# MD_260w.net
KiCad netlist of a schematic drawn in EAGLE
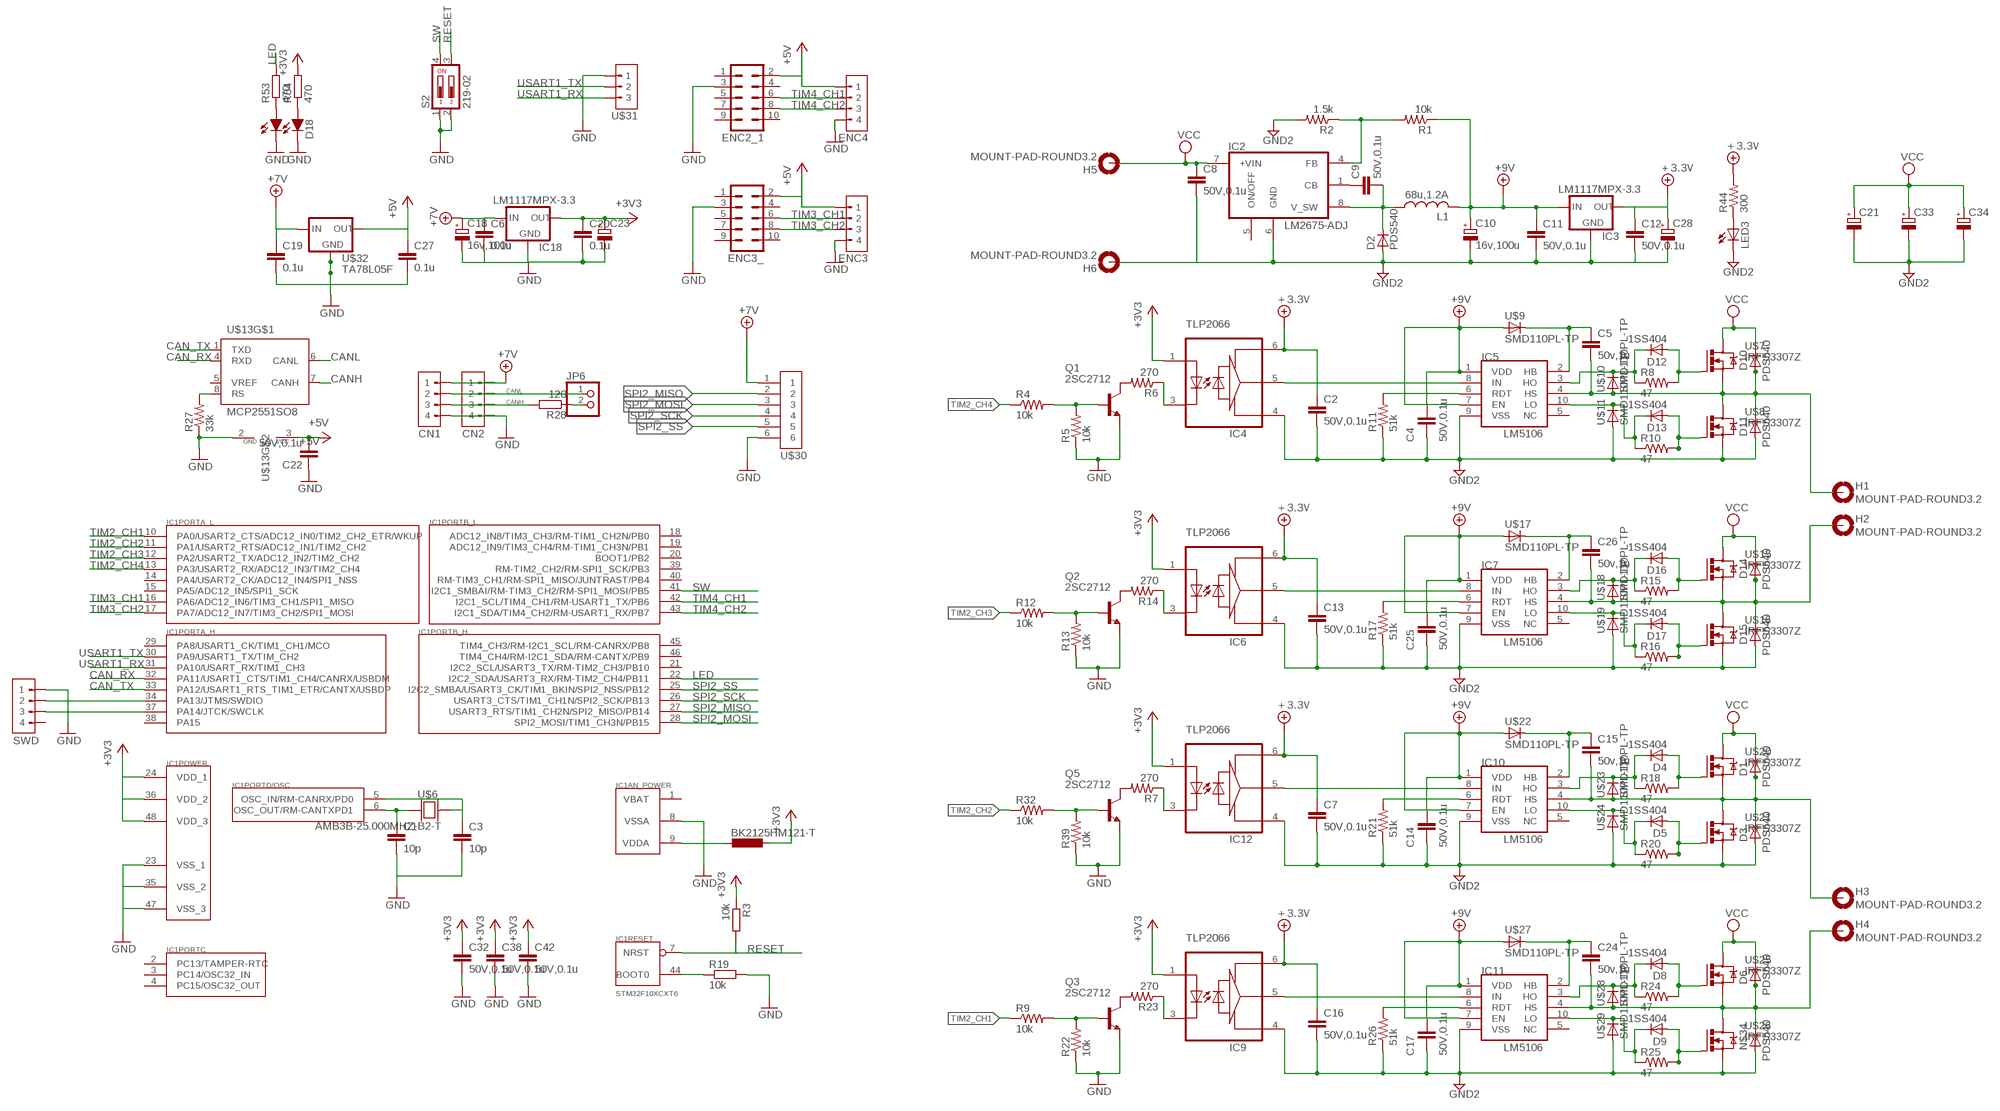
[diagram p0: schematic, sheet 1]

(export (version "E")
  (design (tool "Eeschema 10.0.6"))
  (components
    (comp (ref "BK2125HM121-T")
      (value "L-EUL2012C")
      (footprint "eagle-import:L2012C")
      (libsource (lib "eagle-import") (part "L-EUL2012C"))
    )
    (comp (ref "C1")
      (value "10p")
      (footprint "eagle-import:C0603")
      (libsource (lib "eagle-import") (part "C-EUC0603"))
    )
    (comp (ref "C2")
      (value "50V,0.1u")
      (footprint "eagle-import:C0603")
      (libsource (lib "eagle-import") (part "C-EUC0603"))
    )
    (comp (ref "C3")
      (value "10p")
      (footprint "eagle-import:C0603")
      (libsource (lib "eagle-import") (part "C-EUC0603"))
    )
    (comp (ref "C4")
      (value "50V,0.1u")
      (footprint "eagle-import:C0603")
      (libsource (lib "eagle-import") (part "C-EUC0603"))
    )
    (comp (ref "C5")
      (value "50v,1u")
      (footprint "eagle-import:C0603")
      (libsource (lib "eagle-import") (part "C-EUC0603"))
    )
    (comp (ref "C6")
      (value "0.1u")
      (footprint "eagle-import:C0603")
      (libsource (lib "eagle-import") (part "C-EUC0603"))
    )
    (comp (ref "C7")
      (value "50V,0.1u")
      (footprint "eagle-import:C0603")
      (libsource (lib "eagle-import") (part "C-EUC0603"))
    )
    (comp (ref "C8")
      (value "50V,0.1u")
      (footprint "eagle-import:C0603")
      (libsource (lib "eagle-import") (part "C-EUC0603"))
    )
    (comp (ref "C9")
      (value "50V,0.1u")
      (footprint "eagle-import:C0603")
      (libsource (lib "eagle-import") (part "C-EUC0603"))
    )
    (comp (ref "C10")
      (value "16v,100u")
      (footprint "eagle-import:153CLV-0605")
      (libsource (lib "eagle-import") (part "CPOL-EU153CLV-0605"))
    )
    (comp (ref "C11")
      (value "50V,0.1u")
      (footprint "eagle-import:C0603")
      (libsource (lib "eagle-import") (part "C-EUC0603"))
    )
    (comp (ref "C12")
      (value "50V,0.1u")
      (footprint "eagle-import:C0603")
      (libsource (lib "eagle-import") (part "C-EUC0603"))
    )
    (comp (ref "C13")
      (value "50V,0.1u")
      (footprint "eagle-import:C0603")
      (libsource (lib "eagle-import") (part "C-EUC0603"))
    )
    (comp (ref "C14")
      (value "50V,0.1u")
      (footprint "eagle-import:C0603")
      (libsource (lib "eagle-import") (part "C-EUC0603"))
    )
    (comp (ref "C15")
      (value "50v,1u")
      (footprint "eagle-import:C0603")
      (libsource (lib "eagle-import") (part "C-EUC0603"))
    )
    (comp (ref "C16")
      (value "50V,0.1u")
      (footprint "eagle-import:C0603")
      (libsource (lib "eagle-import") (part "C-EUC0603"))
    )
    (comp (ref "C17")
      (value "50V,0.1u")
      (footprint "eagle-import:C0603")
      (libsource (lib "eagle-import") (part "C-EUC0603"))
    )
    (comp (ref "C18")
      (value "16v,100u")
      (footprint "eagle-import:153CLV-0605")
      (libsource (lib "eagle-import") (part "CPOL-EU153CLV-0605"))
    )
    (comp (ref "C19")
      (value "0.1u")
      (footprint "eagle-import:C0603")
      (libsource (lib "eagle-import") (part "C-EUC0603"))
    )
    (comp (ref "C20")
      (value "0.1u")
      (footprint "eagle-import:C0603K")
      (libsource (lib "eagle-import") (part "resistor_C-EUC0603K"))
    )
    (comp (ref "C21")
      (value "CPOL-EUE7.5-16")
      (footprint "eagle-import:E7,5-16")
      (libsource (lib "eagle-import") (part "CPOL-EUE7.5-16"))
    )
    (comp (ref "C22")
      (value "50V,0.1u")
      (footprint "eagle-import:C0603")
      (libsource (lib "eagle-import") (part "C-EUC0603"))
    )
    (comp (ref "C23")
      (value "CPOL-EU153CLV-0505")
      (footprint "eagle-import:153CLV-0505")
      (libsource (lib "eagle-import") (part "CPOL-EU153CLV-0505"))
    )
    (comp (ref "C24")
      (value "50v,1u")
      (footprint "eagle-import:C0603")
      (libsource (lib "eagle-import") (part "C-EUC0603"))
    )
    (comp (ref "C25")
      (value "50V,0.1u")
      (footprint "eagle-import:C0603")
      (libsource (lib "eagle-import") (part "C-EUC0603"))
    )
    (comp (ref "C26")
      (value "50v,1u")
      (footprint "eagle-import:C0603")
      (libsource (lib "eagle-import") (part "C-EUC0603"))
    )
    (comp (ref "C27")
      (value "0.1u")
      (footprint "eagle-import:C0603")
      (libsource (lib "eagle-import") (part "C-EUC0603"))
    )
    (comp (ref "C28")
      (value "CPOL-EU153CLV-0505")
      (footprint "eagle-import:153CLV-0505")
      (libsource (lib "eagle-import") (part "CPOL-EU153CLV-0505"))
    )
    (comp (ref "C32")
      (value "50V,0.1u")
      (footprint "eagle-import:C0603K")
      (libsource (lib "eagle-import") (part "resistor_C-EUC0603K"))
    )
    (comp (ref "C33")
      (value "CPOL-EUE7.5-16")
      (footprint "eagle-import:E7,5-16")
      (libsource (lib "eagle-import") (part "CPOL-EUE7.5-16"))
    )
    (comp (ref "C34")
      (value "CPOL-EUE7.5-16")
      (footprint "eagle-import:E7,5-16")
      (libsource (lib "eagle-import") (part "CPOL-EUE7.5-16"))
    )
    (comp (ref "C38")
      (value "50V,0.1u")
      (footprint "eagle-import:C0603K")
      (libsource (lib "eagle-import") (part "resistor_C-EUC0603K"))
    )
    (comp (ref "C42")
      (value "50V,0.1u")
      (footprint "eagle-import:C0603K")
      (libsource (lib "eagle-import") (part "resistor_C-EUC0603K"))
    )
    (comp (ref "CN1")
      (value "CN4-JST-XH-TOP")
      (footprint "eagle-import:JST-B4B-XH-A")
      (libsource (lib "eagle-import") (part "CN4-JST-XH-TOP"))
    )
    (comp (ref "CN2")
      (value "CN4-JST-XH-TOP")
      (footprint "eagle-import:JST-B4B-XH-A")
      (libsource (lib "eagle-import") (part "CN4-JST-XH-TOP"))
    )
    (comp (ref "D1")
      (value "PDS540")
      (footprint "eagle-import:POWER_DI_5")
      (libsource (lib "eagle-import") (part "PDS540"))
    )
    (comp (ref "D2")
      (value "PDS540")
      (footprint "eagle-import:POWER_DI_5")
      (libsource (lib "eagle-import") (part "PDS540"))
    )
    (comp (ref "D3")
      (value "PDS540")
      (footprint "eagle-import:POWER_DI_5")
      (libsource (lib "eagle-import") (part "PDS540"))
    )
    (comp (ref "D4")
      (value "1SS404")
      (footprint "eagle-import:USC(1.25X2.5)")
      (libsource (lib "eagle-import") (part "1SS404"))
    )
    (comp (ref "D5")
      (value "1SS404")
      (footprint "eagle-import:USC(1.25X2.5)")
      (libsource (lib "eagle-import") (part "1SS404"))
    )
    (comp (ref "D6")
      (value "PDS540")
      (footprint "eagle-import:POWER_DI_5")
      (libsource (lib "eagle-import") (part "PDS540"))
    )
    (comp (ref "D8")
      (value "1SS404")
      (footprint "eagle-import:USC(1.25X2.5)")
      (libsource (lib "eagle-import") (part "1SS404"))
    )
    (comp (ref "D9")
      (value "1SS404")
      (footprint "eagle-import:USC(1.25X2.5)")
      (libsource (lib "eagle-import") (part "1SS404"))
    )
    (comp (ref "D10")
      (value "PDS540")
      (footprint "eagle-import:POWER_DI_5")
      (libsource (lib "eagle-import") (part "PDS540"))
    )
    (comp (ref "D11")
      (value "PDS540")
      (footprint "eagle-import:POWER_DI_5")
      (libsource (lib "eagle-import") (part "PDS540"))
    )
    (comp (ref "D12")
      (value "1SS404")
      (footprint "eagle-import:USC(1.25X2.5)")
      (libsource (lib "eagle-import") (part "1SS404"))
    )
    (comp (ref "D13")
      (value "1SS404")
      (footprint "eagle-import:USC(1.25X2.5)")
      (libsource (lib "eagle-import") (part "1SS404"))
    )
    (comp (ref "D14")
      (value "PDS540")
      (footprint "eagle-import:POWER_DI_5")
      (libsource (lib "eagle-import") (part "PDS540"))
    )
    (comp (ref "D15")
      (value "PDS540")
      (footprint "eagle-import:POWER_DI_5")
      (libsource (lib "eagle-import") (part "PDS540"))
    )
    (comp (ref "D16")
      (value "1SS404")
      (footprint "eagle-import:USC(1.25X2.5)")
      (libsource (lib "eagle-import") (part "1SS404"))
    )
    (comp (ref "D17")
      (value "1SS404")
      (footprint "eagle-import:USC(1.25X2.5)")
      (libsource (lib "eagle-import") (part "1SS404"))
    )
    (comp (ref "D18")
      (value "SEC2XX4")
      (footprint "eagle-import:LED3025")
      (libsource (lib "eagle-import") (part "SEC2XX4"))
    )
    (comp (ref "ENC2_1")
      (value "ML10L")
      (footprint "eagle-import:ML10L")
      (libsource (lib "eagle-import") (part "ML10L"))
    )
    (comp (ref "ENC3")
      (value "CN4-JST-XH-TOP")
      (footprint "eagle-import:JST-B4B-XH-A")
      (libsource (lib "eagle-import") (part "CN4-JST-XH-TOP"))
    )
    (comp (ref "ENC3_")
      (value "ML10L")
      (footprint "eagle-import:ML10L")
      (libsource (lib "eagle-import") (part "ML10L"))
    )
    (comp (ref "ENC4")
      (value "CN4-JST-XH-TOP")
      (footprint "eagle-import:JST-B4B-XH-A")
      (libsource (lib "eagle-import") (part "CN4-JST-XH-TOP"))
    )
    (comp (ref "H1")
      (value "MOUNT-PAD-ROUND3.2")
      (footprint "eagle-import:3,2-PAD")
      (libsource (lib "eagle-import") (part "MOUNT-PAD-ROUND3.2"))
    )
    (comp (ref "H2")
      (value "MOUNT-PAD-ROUND3.2")
      (footprint "eagle-import:3,2-PAD")
      (libsource (lib "eagle-import") (part "MOUNT-PAD-ROUND3.2"))
    )
    (comp (ref "H3")
      (value "MOUNT-PAD-ROUND3.2")
      (footprint "eagle-import:3,2-PAD")
      (libsource (lib "eagle-import") (part "MOUNT-PAD-ROUND3.2"))
    )
    (comp (ref "H4")
      (value "MOUNT-PAD-ROUND3.2")
      (footprint "eagle-import:3,2-PAD")
      (libsource (lib "eagle-import") (part "MOUNT-PAD-ROUND3.2"))
    )
    (comp (ref "H5")
      (value "MOUNT-PAD-ROUND3.2")
      (footprint "eagle-import:3,2-PAD")
      (libsource (lib "eagle-import") (part "MOUNT-PAD-ROUND3.2"))
    )
    (comp (ref "H6")
      (value "MOUNT-PAD-ROUND3.2")
      (footprint "eagle-import:3,2-PAD")
      (libsource (lib "eagle-import") (part "MOUNT-PAD-ROUND3.2"))
    )
    (comp (ref "IC1")
      (value "STM32F10XCXT6")
      (footprint "eagle-import:TQFP48")
      (libsource (lib "eagle-import") (part "STM32F10XCXT6"))
    )
    (comp (ref "IC2")
      (value "LM2675-ADJ")
      (footprint "eagle-import:SOP8-150")
      (libsource (lib "eagle-import") (part "LM2675"))
    )
    (comp (ref "IC3")
      (value "LM1117MPX-3.3")
      (footprint "eagle-import:SOT223")
      (libsource (lib "eagle-import") (part "LM1117"))
    )
    (comp (ref "IC4")
      (value "TLP2066")
      (footprint "eagle-import:MFSOP6")
      (libsource (lib "eagle-import") (part "TLP117"))
    )
    (comp (ref "IC5")
      (value "LM5106")
      (footprint "eagle-import:MSOP10")
      (libsource (lib "eagle-import") (part "LM5106"))
    )
    (comp (ref "IC6")
      (value "TLP2066")
      (footprint "eagle-import:MFSOP6")
      (libsource (lib "eagle-import") (part "TLP117"))
    )
    (comp (ref "IC7")
      (value "LM5106")
      (footprint "eagle-import:MSOP10")
      (libsource (lib "eagle-import") (part "LM5106"))
    )
    (comp (ref "IC9")
      (value "TLP2066")
      (footprint "eagle-import:MFSOP6")
      (libsource (lib "eagle-import") (part "TLP117"))
    )
    (comp (ref "IC10")
      (value "LM5106")
      (footprint "eagle-import:MSOP10")
      (libsource (lib "eagle-import") (part "LM5106"))
    )
    (comp (ref "IC11")
      (value "LM5106")
      (footprint "eagle-import:MSOP10")
      (libsource (lib "eagle-import") (part "LM5106"))
    )
    (comp (ref "IC12")
      (value "TLP2066")
      (footprint "eagle-import:MFSOP6")
      (libsource (lib "eagle-import") (part "TLP117"))
    )
    (comp (ref "IC18")
      (value "LM1117MPX-3.3")
      (footprint "eagle-import:SOT223")
      (libsource (lib "eagle-import") (part "LM1117"))
    )
    (comp (ref "JP6")
      (value "PINHD-1X2")
      (footprint "eagle-import:1X02")
      (libsource (lib "eagle-import") (part "PINHD-1X2"))
    )
    (comp (ref "L1")
      (value "68u,1.2A")
      (footprint "eagle-import:SLF10145")
      (libsource (lib "eagle-import") (part "SLF10145T"))
    )
    (comp (ref "LED3")
      (value "0603")
      (footprint "eagle-import:0603")
      (libsource (lib "eagle-import") (part "0603"))
    )
    (comp (ref "N$34")
      (value "PDS540")
      (footprint "eagle-import:POWER_DI_5")
      (libsource (lib "eagle-import") (part "PDS540"))
    )
    (comp (ref "Q1")
      (value "2SC2712")
      (footprint "eagle-import:SC-59(TYPE1)")
      (libsource (lib "eagle-import") (part "2SC2712"))
    )
    (comp (ref "Q2")
      (value "2SC2712")
      (footprint "eagle-import:SC-59(TYPE1)")
      (libsource (lib "eagle-import") (part "2SC2712"))
    )
    (comp (ref "Q3")
      (value "2SC2712")
      (footprint "eagle-import:SC-59(TYPE1)")
      (libsource (lib "eagle-import") (part "2SC2712"))
    )
    (comp (ref "Q5")
      (value "2SC2712")
      (footprint "eagle-import:SC-59(TYPE1)")
      (libsource (lib "eagle-import") (part "2SC2712"))
    )
    (comp (ref "R1")
      (value "10k")
      (footprint "eagle-import:R0603")
      (libsource (lib "eagle-import") (part "resistor_R-US_R0603"))
    )
    (comp (ref "R2")
      (value "1.5k")
      (footprint "eagle-import:R0603")
      (libsource (lib "eagle-import") (part "resistor_R-US_R0603"))
    )
    (comp (ref "R3")
      (value "10k")
      (footprint "eagle-import:R0603")
      (libsource (lib "eagle-import") (part "R-EU_R0603"))
    )
    (comp (ref "R4")
      (value "10k")
      (footprint "eagle-import:R0603")
      (libsource (lib "eagle-import") (part "resistor_R-US_R0603"))
    )
    (comp (ref "R5")
      (value "10k")
      (footprint "eagle-import:R0603")
      (libsource (lib "eagle-import") (part "resistor_R-US_R0603"))
    )
    (comp (ref "R6")
      (value "270")
      (footprint "eagle-import:R0603")
      (libsource (lib "eagle-import") (part "resistor_R-US_R0603"))
    )
    (comp (ref "R7")
      (value "270")
      (footprint "eagle-import:R0603")
      (libsource (lib "eagle-import") (part "resistor_R-US_R0603"))
    )
    (comp (ref "R8")
      (value "47")
      (footprint "eagle-import:R0603")
      (libsource (lib "eagle-import") (part "resistor_R-US_R0603"))
    )
    (comp (ref "R9")
      (value "10k")
      (footprint "eagle-import:R0603")
      (libsource (lib "eagle-import") (part "resistor_R-US_R0603"))
    )
    (comp (ref "R10")
      (value "47")
      (footprint "eagle-import:R0603")
      (libsource (lib "eagle-import") (part "resistor_R-US_R0603"))
    )
    (comp (ref "R11")
      (value "51k")
      (footprint "eagle-import:R0603")
      (libsource (lib "eagle-import") (part "R-US_R0603"))
    )
    (comp (ref "R12")
      (value "10k")
      (footprint "eagle-import:R0603")
      (libsource (lib "eagle-import") (part "resistor_R-US_R0603"))
    )
    (comp (ref "R13")
      (value "10k")
      (footprint "eagle-import:R0603")
      (libsource (lib "eagle-import") (part "resistor_R-US_R0603"))
    )
    (comp (ref "R14")
      (value "270")
      (footprint "eagle-import:R0603")
      (libsource (lib "eagle-import") (part "resistor_R-US_R0603"))
    )
    (comp (ref "R15")
      (value "47")
      (footprint "eagle-import:R0603")
      (libsource (lib "eagle-import") (part "resistor_R-US_R0603"))
    )
    (comp (ref "R16")
      (value "47")
      (footprint "eagle-import:R0603")
      (libsource (lib "eagle-import") (part "resistor_R-US_R0603"))
    )
    (comp (ref "R17")
      (value "51k")
      (footprint "eagle-import:R0603")
      (libsource (lib "eagle-import") (part "R-US_R0603"))
    )
    (comp (ref "R18")
      (value "47")
      (footprint "eagle-import:R0603")
      (libsource (lib "eagle-import") (part "resistor_R-US_R0603"))
    )
    (comp (ref "R19")
      (value "10k")
      (footprint "eagle-import:R0603")
      (libsource (lib "eagle-import") (part "R-EU_R0603"))
    )
    (comp (ref "R20")
      (value "47")
      (footprint "eagle-import:R0603")
      (libsource (lib "eagle-import") (part "resistor_R-US_R0603"))
    )
    (comp (ref "R21")
      (value "51k")
      (footprint "eagle-import:R0603")
      (libsource (lib "eagle-import") (part "R-US_R0603"))
    )
    (comp (ref "R22")
      (value "10k")
      (footprint "eagle-import:R0603")
      (libsource (lib "eagle-import") (part "resistor_R-US_R0603"))
    )
    (comp (ref "R23")
      (value "270")
      (footprint "eagle-import:R0603")
      (libsource (lib "eagle-import") (part "resistor_R-US_R0603"))
    )
    (comp (ref "R24")
      (value "47")
      (footprint "eagle-import:R0603")
      (libsource (lib "eagle-import") (part "resistor_R-US_R0603"))
    )
    (comp (ref "R25")
      (value "47")
      (footprint "eagle-import:R0603")
      (libsource (lib "eagle-import") (part "resistor_R-US_R0603"))
    )
    (comp (ref "R26")
      (value "51k")
      (footprint "eagle-import:R0603")
      (libsource (lib "eagle-import") (part "R-US_R0603"))
    )
    (comp (ref "R27")
      (value "33k")
      (footprint "eagle-import:R0603")
      (libsource (lib "eagle-import") (part "resistor_R-US_R0603"))
    )
    (comp (ref "R28")
      (value "120")
      (footprint "eagle-import:R0603")
      (libsource (lib "eagle-import") (part "resistor_R-EU_R0603"))
    )
    (comp (ref "R32")
      (value "10k")
      (footprint "eagle-import:R0603")
      (libsource (lib "eagle-import") (part "resistor_R-US_R0603"))
    )
    (comp (ref "R39")
      (value "10k")
      (footprint "eagle-import:R0603")
      (libsource (lib "eagle-import") (part "resistor_R-US_R0603"))
    )
    (comp (ref "R44")
      (value "300")
      (footprint "eagle-import:R0603")
      (libsource (lib "eagle-import") (part "resistor_R-US_R0603"))
    )
    (comp (ref "R53")
      (value "470")
      (footprint "eagle-import:R0603")
      (libsource (lib "eagle-import") (part "resistor_R-EU_R0603"))
    )
    (comp (ref "R54")
      (value "470")
      (footprint "eagle-import:R0603")
      (libsource (lib "eagle-import") (part "resistor_R-EU_R0603"))
    )
    (comp (ref "S2")
      (value "219-02")
      (footprint "eagle-import:CTS-219-02")
      (libsource (lib "eagle-import") (part "219-02"))
    )
    (comp (ref "SWD")
      (value "TOP_TYPE_4PIN")
      (footprint "eagle-import:TOP_TYPE_4PIN")
      (libsource (lib "eagle-import") (part "TOP_TYPE_4PIN"))
    )
    (comp (ref "U$6")
      (value "AMB3B-25.000MHZ-B2-T")
      (footprint "eagle-import:4LCC")
      (libsource (lib "eagle-import") (part "AMB3B-25.000MHZ-B2-T"))
    )
    (comp (ref "U$7")
      (value "IRFS3307Z")
      (footprint "eagle-import:IRFS3307Z")
      (libsource (lib "eagle-import") (part "IRFS3307Z"))
    )
    (comp (ref "U$8")
      (value "IRFS3307Z")
      (footprint "eagle-import:IRFS3307Z")
      (libsource (lib "eagle-import") (part "IRFS3307Z"))
    )
    (comp (ref "U$9")
      (value "SMD110PL-TP")
      (footprint "eagle-import:SOD123")
      (libsource (lib "eagle-import") (part "SMD110PL-TP"))
    )
    (comp (ref "U$10")
      (value "SMD110PL-TP")
      (footprint "eagle-import:SOD123")
      (libsource (lib "eagle-import") (part "SMD110PL-TP"))
    )
    (comp (ref "U$11")
      (value "SMD110PL-TP")
      (footprint "eagle-import:SOD123")
      (libsource (lib "eagle-import") (part "SMD110PL-TP"))
    )
    (comp (ref "U$13")
      (value "MCP2551SO8")
      (footprint "eagle-import:SO08")
      (libsource (lib "eagle-import") (part "MCP2551SO8"))
    )
    (comp (ref "U$15")
      (value "IRFS3307Z")
      (footprint "eagle-import:IRFS3307Z")
      (libsource (lib "eagle-import") (part "IRFS3307Z"))
    )
    (comp (ref "U$16")
      (value "IRFS3307Z")
      (footprint "eagle-import:IRFS3307Z")
      (libsource (lib "eagle-import") (part "IRFS3307Z"))
    )
    (comp (ref "U$17")
      (value "SMD110PL-TP")
      (footprint "eagle-import:SOD123")
      (libsource (lib "eagle-import") (part "SMD110PL-TP"))
    )
    (comp (ref "U$18")
      (value "SMD110PL-TP")
      (footprint "eagle-import:SOD123")
      (libsource (lib "eagle-import") (part "SMD110PL-TP"))
    )
    (comp (ref "U$19")
      (value "SMD110PL-TP")
      (footprint "eagle-import:SOD123")
      (libsource (lib "eagle-import") (part "SMD110PL-TP"))
    )
    (comp (ref "U$20")
      (value "IRFS3307Z")
      (footprint "eagle-import:IRFS3307Z")
      (libsource (lib "eagle-import") (part "IRFS3307Z"))
    )
    (comp (ref "U$21")
      (value "IRFS3307Z")
      (footprint "eagle-import:IRFS3307Z")
      (libsource (lib "eagle-import") (part "IRFS3307Z"))
    )
    (comp (ref "U$22")
      (value "SMD110PL-TP")
      (footprint "eagle-import:SOD123")
      (libsource (lib "eagle-import") (part "SMD110PL-TP"))
    )
    (comp (ref "U$23")
      (value "SMD110PL-TP")
      (footprint "eagle-import:SOD123")
      (libsource (lib "eagle-import") (part "SMD110PL-TP"))
    )
    (comp (ref "U$24")
      (value "SMD110PL-TP")
      (footprint "eagle-import:SOD123")
      (libsource (lib "eagle-import") (part "SMD110PL-TP"))
    )
    (comp (ref "U$25")
      (value "IRFS3307Z")
      (footprint "eagle-import:IRFS3307Z")
      (libsource (lib "eagle-import") (part "IRFS3307Z"))
    )
    (comp (ref "U$26")
      (value "IRFS3307Z")
      (footprint "eagle-import:IRFS3307Z")
      (libsource (lib "eagle-import") (part "IRFS3307Z"))
    )
    (comp (ref "U$27")
      (value "SMD110PL-TP")
      (footprint "eagle-import:SOD123")
      (libsource (lib "eagle-import") (part "SMD110PL-TP"))
    )
    (comp (ref "U$28")
      (value "SMD110PL-TP")
      (footprint "eagle-import:SOD123")
      (libsource (lib "eagle-import") (part "SMD110PL-TP"))
    )
    (comp (ref "U$29")
      (value "SMD110PL-TP")
      (footprint "eagle-import:SOD123")
      (libsource (lib "eagle-import") (part "SMD110PL-TP"))
    )
    (comp (ref "U$30")
      (value "CN6")
      (footprint "eagle-import:JST-B6B-XH-A")
      (libsource (lib "eagle-import") (part "CN6"))
    )
    (comp (ref "U$31")
      (value "TOP_TYPE_3PIN")
      (footprint "eagle-import:TOP_TYPE_3PIN")
      (libsource (lib "eagle-import") (part "TOP_TYPE_3PIN"))
    )
    (comp (ref "U$32")
      (value "TA78L05F")
      (footprint "eagle-import:SOT89")
      (libsource (lib "eagle-import") (part "TA78L05F"))
    )
  )
  (nets
    (net (code "1") (name "+3V3") (class "Default")
      (node (ref "BK2125HM121-T") (pin "1") (pinfunction "1_1") (pintype "passive"))
      (node (ref "C20") (pin "1") (pinfunction "1_1") (pintype "passive"))
      (node (ref "C23") (pin "+") (pinfunction "+_+") (pintype "passive"))
      (node (ref "C32") (pin "1") (pinfunction "1_1") (pintype "passive"))
      (node (ref "C38") (pin "1") (pinfunction "1_1") (pintype "passive"))
      (node (ref "C42") (pin "1") (pinfunction "1_1") (pintype "passive"))
      (node (ref "IC1") (pin "24") (pinfunction "VDD_1_24") (pintype "power_in"))
      (node (ref "IC1") (pin "36") (pinfunction "VDD_2_36") (pintype "power_in"))
      (node (ref "IC1") (pin "48") (pinfunction "VDD_3_48") (pintype "power_in"))
      (node (ref "IC12") (pin "1") (pinfunction "1_1") (pintype "input"))
      (node (ref "IC18") (pin "2") (pinfunction "OUT1_2") (pintype "passive"))
      (node (ref "IC18") (pin "4") (pinfunction "OUT_4") (pintype "passive"))
      (node (ref "IC4") (pin "1") (pinfunction "1_1") (pintype "input"))
      (node (ref "IC6") (pin "1") (pinfunction "1_1") (pintype "input"))
      (node (ref "IC9") (pin "1") (pinfunction "1_1") (pintype "input"))
      (node (ref "R3") (pin "1") (pinfunction "1_1") (pintype "passive"))
      (node (ref "R54") (pin "2") (pinfunction "2_2") (pintype "passive"))
    )
    (net (code "2") (name "+5V") (class "Default")
      (node (ref "C22") (pin "2") (pinfunction "2_2") (pintype "passive"))
      (node (ref "C27") (pin "1") (pinfunction "1_1") (pintype "passive"))
      (node (ref "ENC2_1") (pin "2") (pinfunction "2_2") (pintype "passive"))
      (node (ref "ENC3") (pin "1") (pinfunction "1_1") (pintype "passive"))
      (node (ref "ENC3_") (pin "2") (pinfunction "2_2") (pintype "passive"))
      (node (ref "ENC4") (pin "1") (pinfunction "1_1") (pintype "passive"))
      (node (ref "U$13") (pin "3") (pinfunction "VCC_3") (pintype "power_in"))
      (node (ref "U$32") (pin "1") (pinfunction "OUT_1") (pintype "passive"))
    )
    (net (code "3") (name "+7V") (class "Default")
      (node (ref "C18") (pin "+") (pinfunction "+_+") (pintype "passive"))
      (node (ref "C19") (pin "1") (pinfunction "1_1") (pintype "passive"))
      (node (ref "C6") (pin "1") (pinfunction "1_1") (pintype "passive"))
      (node (ref "CN1") (pin "1") (pinfunction "1_1") (pintype "passive"))
      (node (ref "CN2") (pin "1") (pinfunction "1_1") (pintype "passive"))
      (node (ref "IC18") (pin "3") (pinfunction "IN_3") (pintype "input"))
      (node (ref "U$30") (pin "1") (pinfunction "1_1") (pintype "passive"))
      (node (ref "U$32") (pin "3") (pinfunction "IN_3") (pintype "input"))
    )
    (net (code "4") (name "+9V") (class "Default")
      (node (ref "C10") (pin "+") (pinfunction "+_+") (pintype "passive"))
      (node (ref "C11") (pin "1") (pinfunction "1_1") (pintype "passive"))
      (node (ref "C14") (pin "1") (pinfunction "1_1") (pintype "passive"))
      (node (ref "C17") (pin "1") (pinfunction "1_1") (pintype "passive"))
      (node (ref "C25") (pin "1") (pinfunction "1_1") (pintype "passive"))
      (node (ref "C4") (pin "1") (pinfunction "1_1") (pintype "passive"))
      (node (ref "IC10") (pin "1") (pinfunction "VDD_1") (pintype "power_in"))
      (node (ref "IC10") (pin "7") (pinfunction "EN_7") (pintype "input"))
      (node (ref "IC11") (pin "1") (pinfunction "VDD_1") (pintype "power_in"))
      (node (ref "IC11") (pin "7") (pinfunction "EN_7") (pintype "input"))
      (node (ref "IC3") (pin "3") (pinfunction "IN_3") (pintype "input"))
      (node (ref "IC5") (pin "1") (pinfunction "VDD_1") (pintype "power_in"))
      (node (ref "IC5") (pin "7") (pinfunction "EN_7") (pintype "input"))
      (node (ref "IC7") (pin "1") (pinfunction "VDD_1") (pintype "power_in"))
      (node (ref "IC7") (pin "7") (pinfunction "EN_7") (pintype "input"))
      (node (ref "L1") (pin "P$2") (pinfunction "2_P$2") (pintype "passive"))
      (node (ref "R1") (pin "1") (pinfunction "1_1") (pintype "passive"))
      (node (ref "U$17") (pin "A") (pinfunction "A_A") (pintype "passive"))
      (node (ref "U$22") (pin "A") (pinfunction "A_A") (pintype "passive"))
      (node (ref "U$27") (pin "A") (pinfunction "A_A") (pintype "passive"))
      (node (ref "U$9") (pin "A") (pinfunction "A_A") (pintype "passive"))
    )
    (net (code "5") (name "/CANH") (class "Default")
      (node (ref "CN1") (pin "3") (pinfunction "3_3") (pintype "passive"))
      (node (ref "CN2") (pin "3") (pinfunction "3_3") (pintype "passive"))
      (node (ref "R28") (pin "2") (pinfunction "2_2") (pintype "passive"))
      (node (ref "U$13") (pin "7") (pinfunction "CANH_7") (pintype "bidirectional"))
    )
    (net (code "6") (name "/CANL") (class "Default")
      (node (ref "CN1") (pin "2") (pinfunction "2_2") (pintype "passive"))
      (node (ref "CN2") (pin "2") (pinfunction "2_2") (pintype "passive"))
      (node (ref "JP6") (pin "1") (pinfunction "1_1") (pintype "passive"))
      (node (ref "U$13") (pin "6") (pinfunction "CANL_6") (pintype "bidirectional"))
    )
    (net (code "7") (name "/CAN_RX") (class "Default")
      (node (ref "IC1") (pin "32") (pinfunction "PA11/USART1_CTS/TIM1_CH4/CANRX/USBDM_32") (pintype "bidirectional"))
      (node (ref "U$13") (pin "4") (pinfunction "RXD_4") (pintype "bidirectional"))
    )
    (net (code "8") (name "/CAN_TX") (class "Default")
      (node (ref "IC1") (pin "33") (pinfunction "PA12/USART1_RTS_TIM1_ETR/CANTX/USBDP_33") (pintype "bidirectional"))
      (node (ref "U$13") (pin "1") (pinfunction "TXD_1") (pintype "bidirectional"))
    )
    (net (code "9") (name "/LED") (class "Default")
      (node (ref "IC1") (pin "22") (pinfunction "I2C2_SDA/USART3_RX/RM-TIM2_CH4/PB11_22") (pintype "bidirectional"))
      (node (ref "R53") (pin "2") (pinfunction "2_2") (pintype "passive"))
    )
    (net (code "10") (name "/RESET") (class "Default")
      (node (ref "IC1") (pin "7") (pinfunction "NRST_7") (pintype "input"))
      (node (ref "R3") (pin "2") (pinfunction "2_2") (pintype "passive"))
      (node (ref "S2") (pin "3") (pinfunction "3_3") (pintype "passive"))
    )
    (net (code "11") (name "/SW") (class "Default")
      (node (ref "IC1") (pin "41") (pinfunction "I2C1_SMBAI/RM-TIM3_CH2/RM-SPI1_MOSI/PB5_41") (pintype "bidirectional"))
      (node (ref "S2") (pin "4") (pinfunction "4_4") (pintype "passive"))
    )
    (net (code "12") (name "/TIM3_CH1") (class "Default")
      (node (ref "ENC3") (pin "2") (pinfunction "2_2") (pintype "passive"))
      (node (ref "ENC3_") (pin "6") (pinfunction "6_6") (pintype "passive"))
      (node (ref "IC1") (pin "16") (pinfunction "PA6/ADC12_IN6/TIM3_CH1/SPI1_MISO_16") (pintype "bidirectional"))
    )
    (net (code "13") (name "/TIM3_CH2") (class "Default")
      (node (ref "ENC3") (pin "3") (pinfunction "3_3") (pintype "passive"))
      (node (ref "ENC3_") (pin "8") (pinfunction "8_8") (pintype "passive"))
      (node (ref "IC1") (pin "17") (pinfunction "PA7/ADC12_IN7/TIM3_CH2/SPI1_MOSI_17") (pintype "bidirectional"))
    )
    (net (code "14") (name "/TIM4_CH1") (class "Default")
      (node (ref "ENC2_1") (pin "6") (pinfunction "6_6") (pintype "passive"))
      (node (ref "ENC4") (pin "2") (pinfunction "2_2") (pintype "passive"))
      (node (ref "IC1") (pin "42") (pinfunction "I2C1_SCL/TIM4_CH1/RM-USART1_TX/PB6_42") (pintype "bidirectional"))
    )
    (net (code "15") (name "/TIM4_CH2") (class "Default")
      (node (ref "ENC2_1") (pin "8") (pinfunction "8_8") (pintype "passive"))
      (node (ref "ENC4") (pin "3") (pinfunction "3_3") (pintype "passive"))
      (node (ref "IC1") (pin "43") (pinfunction "I2C1_SDA/TIM4_CH2/RM-USART1_RX/PB7_43") (pintype "bidirectional"))
    )
    (net (code "16") (name "/USART1_RX") (class "Default")
      (node (ref "IC1") (pin "31") (pinfunction "PA10/USART_RX/TIM1_CH3_31") (pintype "bidirectional"))
      (node (ref "U$31") (pin "3") (pinfunction "3_3") (pintype "passive"))
    )
    (net (code "17") (name "/USART1_TX") (class "Default")
      (node (ref "IC1") (pin "30") (pinfunction "PA9/USART1_TX/TIM_CH2_30") (pintype "bidirectional"))
      (node (ref "U$31") (pin "2") (pinfunction "2_2") (pintype "passive"))
    )
    (net (code "18") (name "/VBAT") (class "Default")
      (node (ref "IC1") (pin "1") (pinfunction "VBAT_1") (pintype "power_in"))
    )
    (net (code "19") (name "GND") (class "Default")
      (node (ref "C1") (pin "2") (pinfunction "2_2") (pintype "passive"))
      (node (ref "C18") (pin "-") (pinfunction "-_-") (pintype "passive"))
      (node (ref "C19") (pin "2") (pinfunction "2_2") (pintype "passive"))
      (node (ref "C20") (pin "2") (pinfunction "2_2") (pintype "passive"))
      (node (ref "C22") (pin "1") (pinfunction "1_1") (pintype "passive"))
      (node (ref "C23") (pin "-") (pinfunction "-_-") (pintype "passive"))
      (node (ref "C27") (pin "2") (pinfunction "2_2") (pintype "passive"))
      (node (ref "C3") (pin "2") (pinfunction "2_2") (pintype "passive"))
      (node (ref "C32") (pin "2") (pinfunction "2_2") (pintype "passive"))
      (node (ref "C38") (pin "2") (pinfunction "2_2") (pintype "passive"))
      (node (ref "C42") (pin "2") (pinfunction "2_2") (pintype "passive"))
      (node (ref "C6") (pin "2") (pinfunction "2_2") (pintype "passive"))
      (node (ref "CN1") (pin "4") (pinfunction "4_4") (pintype "passive"))
      (node (ref "CN2") (pin "4") (pinfunction "4_4") (pintype "passive"))
      (node (ref "D18") (pin "1") (pinfunction "C0_1") (pintype "passive"))
      (node (ref "D18") (pin "2") (pinfunction "C1_2") (pintype "passive"))
      (node (ref "ENC2_1") (pin "3") (pinfunction "3_3") (pintype "passive"))
      (node (ref "ENC3") (pin "4") (pinfunction "4_4") (pintype "passive"))
      (node (ref "ENC3_") (pin "3") (pinfunction "3_3") (pintype "passive"))
      (node (ref "ENC4") (pin "4") (pinfunction "4_4") (pintype "passive"))
      (node (ref "IC1") (pin "23") (pinfunction "VSS_1_23") (pintype "power_in"))
      (node (ref "IC1") (pin "35") (pinfunction "VSS_2_35") (pintype "power_in"))
      (node (ref "IC1") (pin "47") (pinfunction "VSS_3_47") (pintype "power_in"))
      (node (ref "IC1") (pin "8") (pinfunction "VSSA_8") (pintype "power_in"))
      (node (ref "IC18") (pin "1") (pinfunction "GND_1") (pintype "input"))
      (node (ref "Q1") (pin "E") (pinfunction "E_E") (pintype "passive"))
      (node (ref "Q2") (pin "E") (pinfunction "E_E") (pintype "passive"))
      (node (ref "Q3") (pin "E") (pinfunction "E_E") (pintype "passive"))
      (node (ref "Q5") (pin "E") (pinfunction "E_E") (pintype "passive"))
      (node (ref "R13") (pin "1") (pinfunction "1_1") (pintype "passive"))
      (node (ref "R19") (pin "2") (pinfunction "2_2") (pintype "passive"))
      (node (ref "R22") (pin "1") (pinfunction "1_1") (pintype "passive"))
      (node (ref "R27") (pin "1") (pinfunction "1_1") (pintype "passive"))
      (node (ref "R39") (pin "1") (pinfunction "1_1") (pintype "passive"))
      (node (ref "R5") (pin "1") (pinfunction "1_1") (pintype "passive"))
      (node (ref "S2") (pin "1") (pinfunction "1_1") (pintype "passive"))
      (node (ref "S2") (pin "2") (pinfunction "2_2") (pintype "passive"))
      (node (ref "SWD") (pin "1") (pinfunction "1_1") (pintype "passive"))
      (node (ref "U$13") (pin "2") (pinfunction "GND_2") (pintype "power_in"))
      (node (ref "U$30") (pin "6") (pinfunction "6_6") (pintype "passive"))
      (node (ref "U$31") (pin "1") (pinfunction "1_1") (pintype "passive"))
      (node (ref "U$32") (pin "2") (pinfunction "GND_2") (pintype "input"))
      (node (ref "U$32") (pin "2@1") (pinfunction "GND1_2@1") (pintype "input"))
    )
    (net (code "20") (name "GND2") (class "Default")
      (node (ref "C10") (pin "-") (pinfunction "-_-") (pintype "passive"))
      (node (ref "C11") (pin "2") (pinfunction "2_2") (pintype "passive"))
      (node (ref "C12") (pin "2") (pinfunction "2_2") (pintype "passive"))
      (node (ref "C13") (pin "2") (pinfunction "2_2") (pintype "passive"))
      (node (ref "C14") (pin "2") (pinfunction "2_2") (pintype "passive"))
      (node (ref "C16") (pin "2") (pinfunction "2_2") (pintype "passive"))
      (node (ref "C17") (pin "2") (pinfunction "2_2") (pintype "passive"))
      (node (ref "C2") (pin "2") (pinfunction "2_2") (pintype "passive"))
      (node (ref "C21") (pin "-") (pinfunction "-_-") (pintype "passive"))
      (node (ref "C25") (pin "2") (pinfunction "2_2") (pintype "passive"))
      (node (ref "C28") (pin "-") (pinfunction "-_-") (pintype "passive"))
      (node (ref "C33") (pin "-") (pinfunction "-_-") (pintype "passive"))
      (node (ref "C34") (pin "-") (pinfunction "-_-") (pintype "passive"))
      (node (ref "C4") (pin "2") (pinfunction "2_2") (pintype "passive"))
      (node (ref "C7") (pin "2") (pinfunction "2_2") (pintype "passive"))
      (node (ref "C8") (pin "2") (pinfunction "2_2") (pintype "passive"))
      (node (ref "D11") (pin "A1") (pinfunction "A1_A1") (pintype "passive"))
      (node (ref "D11") (pin "A2") (pinfunction "A_A2") (pintype "passive"))
      (node (ref "D15") (pin "A1") (pinfunction "A1_A1") (pintype "passive"))
      (node (ref "D15") (pin "A2") (pinfunction "A_A2") (pintype "passive"))
      (node (ref "D2") (pin "A1") (pinfunction "A1_A1") (pintype "passive"))
      (node (ref "D2") (pin "A2") (pinfunction "A_A2") (pintype "passive"))
      (node (ref "D3") (pin "A1") (pinfunction "A1_A1") (pintype "passive"))
      (node (ref "D3") (pin "A2") (pinfunction "A_A2") (pintype "passive"))
      (node (ref "H6") (pin "B3,2") (pinfunction "MOUNT_B3,2") (pintype "passive"))
      (node (ref "IC10") (pin "9") (pinfunction "VSS_9") (pintype "power_in"))
      (node (ref "IC11") (pin "9") (pinfunction "VSS_9") (pintype "power_in"))
      (node (ref "IC12") (pin "4") (pinfunction "GND_4") (pintype "power_in"))
      (node (ref "IC2") (pin "6") (pinfunction "GND_6") (pintype "power_in"))
      (node (ref "IC3") (pin "1") (pinfunction "GND_1") (pintype "input"))
      (node (ref "IC4") (pin "4") (pinfunction "GND_4") (pintype "power_in"))
      (node (ref "IC5") (pin "9") (pinfunction "VSS_9") (pintype "power_in"))
      (node (ref "IC6") (pin "4") (pinfunction "GND_4") (pintype "power_in"))
      (node (ref "IC7") (pin "9") (pinfunction "VSS_9") (pintype "power_in"))
      (node (ref "IC9") (pin "4") (pinfunction "GND_4") (pintype "power_in"))
      (node (ref "LED3") (pin "C") (pinfunction "C_C") (pintype "passive"))
      (node (ref "N$34") (pin "A1") (pinfunction "A1_A1") (pintype "passive"))
      (node (ref "N$34") (pin "A2") (pinfunction "A_A2") (pintype "passive"))
      (node (ref "R11") (pin "1") (pinfunction "1_1") (pintype "passive"))
      (node (ref "R17") (pin "1") (pinfunction "1_1") (pintype "passive"))
      (node (ref "R2") (pin "2") (pinfunction "2_2") (pintype "passive"))
      (node (ref "R21") (pin "1") (pinfunction "1_1") (pintype "passive"))
      (node (ref "R26") (pin "1") (pinfunction "1_1") (pintype "passive"))
      (node (ref "U$11") (pin "A") (pinfunction "A_A") (pintype "passive"))
      (node (ref "U$16") (pin "3") (pinfunction "S_3") (pintype "passive"))
      (node (ref "U$19") (pin "A") (pinfunction "A_A") (pintype "passive"))
      (node (ref "U$21") (pin "3") (pinfunction "S_3") (pintype "passive"))
      (node (ref "U$24") (pin "A") (pinfunction "A_A") (pintype "passive"))
      (node (ref "U$26") (pin "3") (pinfunction "S_3") (pintype "passive"))
      (node (ref "U$29") (pin "A") (pinfunction "A_A") (pintype "passive"))
      (node (ref "U$8") (pin "3") (pinfunction "S_3") (pintype "passive"))
    )
    (net (code "21") (name "Net-(D1-A)") (class "Default")
      (node (ref "C15") (pin "2") (pinfunction "2_2") (pintype "passive"))
      (node (ref "D1") (pin "A1") (pinfunction "A1_A1") (pintype "passive"))
      (node (ref "D1") (pin "A2") (pinfunction "A_A2") (pintype "passive"))
      (node (ref "D3") (pin "K") (pinfunction "C_K") (pintype "passive"))
      (node (ref "H3") (pin "B3,2") (pinfunction "MOUNT_B3,2") (pintype "passive"))
      (node (ref "IC10") (pin "4") (pinfunction "HS_4") (pintype "passive"))
      (node (ref "U$20") (pin "3") (pinfunction "S_3") (pintype "passive"))
      (node (ref "U$21") (pin "2") (pinfunction "D1_2") (pintype "passive"))
      (node (ref "U$23") (pin "A") (pinfunction "A_A") (pintype "passive"))
    )
    (net (code "22") (name "Net-(D2-C)") (class "Default")
      (node (ref "C9") (pin "2") (pinfunction "2_2") (pintype "passive"))
      (node (ref "D2") (pin "K") (pinfunction "C_K") (pintype "passive"))
      (node (ref "IC2") (pin "8") (pinfunction "V_SW_8") (pintype "power_in"))
      (node (ref "L1") (pin "P$1") (pinfunction "1_P$1") (pintype "passive"))
    )
    (net (code "23") (name "Net-(D4-C)") (class "Default")
      (node (ref "D4") (pin "K") (pinfunction "C_K") (pintype "passive"))
      (node (ref "IC10") (pin "3") (pinfunction "HO_3") (pintype "output"))
      (node (ref "R18") (pin "1") (pinfunction "1_1") (pintype "passive"))
      (node (ref "U$23") (pin "K") (pinfunction "C_K") (pintype "passive"))
    )
    (net (code "24") (name "Net-(D5-C)") (class "Default")
      (node (ref "D5") (pin "K") (pinfunction "C_K") (pintype "passive"))
      (node (ref "IC10") (pin "10") (pinfunction "LO_10") (pintype "output"))
      (node (ref "R20") (pin "1") (pinfunction "1_1") (pintype "passive"))
      (node (ref "U$24") (pin "K") (pinfunction "C_K") (pintype "passive"))
    )
    (net (code "25") (name "Net-(D6-A)") (class "Default")
      (node (ref "C24") (pin "2") (pinfunction "2_2") (pintype "passive"))
      (node (ref "D6") (pin "A1") (pinfunction "A1_A1") (pintype "passive"))
      (node (ref "D6") (pin "A2") (pinfunction "A_A2") (pintype "passive"))
      (node (ref "H4") (pin "B3,2") (pinfunction "MOUNT_B3,2") (pintype "passive"))
      (node (ref "IC11") (pin "4") (pinfunction "HS_4") (pintype "passive"))
      (node (ref "N$34") (pin "K") (pinfunction "C_K") (pintype "passive"))
      (node (ref "U$25") (pin "3") (pinfunction "S_3") (pintype "passive"))
      (node (ref "U$26") (pin "2") (pinfunction "D1_2") (pintype "passive"))
      (node (ref "U$28") (pin "A") (pinfunction "A_A") (pintype "passive"))
    )
    (net (code "26") (name "Net-(D8-C)") (class "Default")
      (node (ref "D8") (pin "K") (pinfunction "C_K") (pintype "passive"))
      (node (ref "IC11") (pin "3") (pinfunction "HO_3") (pintype "output"))
      (node (ref "R24") (pin "1") (pinfunction "1_1") (pintype "passive"))
      (node (ref "U$28") (pin "K") (pinfunction "C_K") (pintype "passive"))
    )
    (net (code "27") (name "Net-(D9-C)") (class "Default")
      (node (ref "D9") (pin "K") (pinfunction "C_K") (pintype "passive"))
      (node (ref "IC11") (pin "10") (pinfunction "LO_10") (pintype "output"))
      (node (ref "R25") (pin "1") (pinfunction "1_1") (pintype "passive"))
      (node (ref "U$29") (pin "K") (pinfunction "C_K") (pintype "passive"))
    )
    (net (code "28") (name "Net-(D10-A)") (class "Default")
      (node (ref "C5") (pin "2") (pinfunction "2_2") (pintype "passive"))
      (node (ref "D10") (pin "A1") (pinfunction "A1_A1") (pintype "passive"))
      (node (ref "D10") (pin "A2") (pinfunction "A_A2") (pintype "passive"))
      (node (ref "D11") (pin "K") (pinfunction "C_K") (pintype "passive"))
      (node (ref "H1") (pin "B3,2") (pinfunction "MOUNT_B3,2") (pintype "passive"))
      (node (ref "IC5") (pin "4") (pinfunction "HS_4") (pintype "passive"))
      (node (ref "U$10") (pin "A") (pinfunction "A_A") (pintype "passive"))
      (node (ref "U$7") (pin "3") (pinfunction "S_3") (pintype "passive"))
      (node (ref "U$8") (pin "2") (pinfunction "D1_2") (pintype "passive"))
    )
    (net (code "29") (name "Net-(D12-C)") (class "Default")
      (node (ref "D12") (pin "K") (pinfunction "C_K") (pintype "passive"))
      (node (ref "IC5") (pin "3") (pinfunction "HO_3") (pintype "output"))
      (node (ref "R8") (pin "1") (pinfunction "1_1") (pintype "passive"))
      (node (ref "U$10") (pin "K") (pinfunction "C_K") (pintype "passive"))
    )
    (net (code "30") (name "Net-(D13-C)") (class "Default")
      (node (ref "D13") (pin "K") (pinfunction "C_K") (pintype "passive"))
      (node (ref "IC5") (pin "10") (pinfunction "LO_10") (pintype "output"))
      (node (ref "R10") (pin "1") (pinfunction "1_1") (pintype "passive"))
      (node (ref "U$11") (pin "K") (pinfunction "C_K") (pintype "passive"))
    )
    (net (code "31") (name "Net-(D14-A)") (class "Default")
      (node (ref "C26") (pin "2") (pinfunction "2_2") (pintype "passive"))
      (node (ref "D14") (pin "A1") (pinfunction "A1_A1") (pintype "passive"))
      (node (ref "D14") (pin "A2") (pinfunction "A_A2") (pintype "passive"))
      (node (ref "D15") (pin "K") (pinfunction "C_K") (pintype "passive"))
      (node (ref "H2") (pin "B3,2") (pinfunction "MOUNT_B3,2") (pintype "passive"))
      (node (ref "IC7") (pin "4") (pinfunction "HS_4") (pintype "passive"))
      (node (ref "U$15") (pin "3") (pinfunction "S_3") (pintype "passive"))
      (node (ref "U$16") (pin "2") (pinfunction "D1_2") (pintype "passive"))
      (node (ref "U$18") (pin "A") (pinfunction "A_A") (pintype "passive"))
    )
    (net (code "32") (name "Net-(D16-C)") (class "Default")
      (node (ref "D16") (pin "K") (pinfunction "C_K") (pintype "passive"))
      (node (ref "IC7") (pin "3") (pinfunction "HO_3") (pintype "output"))
      (node (ref "R15") (pin "1") (pinfunction "1_1") (pintype "passive"))
      (node (ref "U$18") (pin "K") (pinfunction "C_K") (pintype "passive"))
    )
    (net (code "33") (name "Net-(D17-C)") (class "Default")
      (node (ref "D17") (pin "K") (pinfunction "C_K") (pintype "passive"))
      (node (ref "IC7") (pin "10") (pinfunction "LO_10") (pintype "output"))
      (node (ref "R16") (pin "1") (pinfunction "1_1") (pintype "passive"))
      (node (ref "U$19") (pin "K") (pinfunction "C_K") (pintype "passive"))
    )
    (net (code "34") (name "Net-(D18-A0)") (class "Default")
      (node (ref "D18") (pin "4") (pinfunction "A0_4") (pintype "passive"))
      (node (ref "R54") (pin "1") (pinfunction "1_1") (pintype "passive"))
    )
    (net (code "35") (name "Net-(D18-A1)") (class "Default")
      (node (ref "D18") (pin "3") (pinfunction "A1_3") (pintype "passive"))
      (node (ref "R53") (pin "1") (pinfunction "1_1") (pintype "passive"))
    )
    (net (code "36") (name "Net-(IC1A-VDDA)") (class "Default")
      (node (ref "BK2125HM121-T") (pin "2") (pinfunction "2_2") (pintype "passive"))
      (node (ref "IC1") (pin "9") (pinfunction "VDDA_9") (pintype "power_in"))
    )
    (net (code "37") (name "Net-(IC1B-PA13{slash}JTMS{slash}SWDIO)") (class "Default")
      (node (ref "IC1") (pin "34") (pinfunction "PA13/JTMS/SWDIO_34") (pintype "bidirectional"))
      (node (ref "SWD") (pin "2") (pinfunction "2_2") (pintype "passive"))
    )
    (net (code "38") (name "Net-(IC1B-PA14{slash}JTCK{slash}SWCLK)") (class "Default")
      (node (ref "IC1") (pin "37") (pinfunction "PA14/JTCK/SWCLK_37") (pintype "bidirectional"))
      (node (ref "SWD") (pin "3") (pinfunction "3_3") (pintype "passive"))
    )
    (net (code "39") (name "Net-(IC1G-OSC_IN{slash}RM-CANRX{slash}PD0)") (class "Default")
      (node (ref "C3") (pin "1") (pinfunction "1_1") (pintype "passive"))
      (node (ref "IC1") (pin "5") (pinfunction "OSC_IN/RM-CANRX/PD0_5") (pintype "bidirectional"))
      (node (ref "U$6") (pin "3") (pinfunction "P$2_3") (pintype "bidirectional"))
    )
    (net (code "40") (name "Net-(IC1G-OSC_OUT{slash}RM-CANTXPD1)") (class "Default")
      (node (ref "C1") (pin "1") (pinfunction "1_1") (pintype "passive"))
      (node (ref "IC1") (pin "6") (pinfunction "OSC_OUT/RM-CANTXPD1_6") (pintype "bidirectional"))
      (node (ref "U$6") (pin "1") (pinfunction "P$1_1") (pintype "bidirectional"))
    )
    (net (code "41") (name "Net-(IC1I-BOOT0)") (class "Default")
      (node (ref "IC1") (pin "44") (pinfunction "BOOT0_44") (pintype "input"))
      (node (ref "R19") (pin "1") (pinfunction "1_1") (pintype "passive"))
    )
    (net (code "42") (name "Net-(IC2-CB)") (class "Default")
      (node (ref "C9") (pin "1") (pinfunction "1_1") (pintype "passive"))
      (node (ref "IC2") (pin "1") (pinfunction "CB_1") (pintype "passive"))
    )
    (net (code "43") (name "Net-(IC2-FB)") (class "Default")
      (node (ref "IC2") (pin "4") (pinfunction "FB_4") (pintype "input"))
      (node (ref "R1") (pin "2") (pinfunction "2_2") (pintype "passive"))
      (node (ref "R2") (pin "1") (pinfunction "1_1") (pintype "passive"))
    )
    (net (code "44") (name "Net-(IC4-Pad3)") (class "Default")
      (node (ref "IC4") (pin "3") (pinfunction "3_3") (pintype "output"))
      (node (ref "R6") (pin "1") (pinfunction "1_1") (pintype "passive"))
    )
    (net (code "45") (name "Net-(IC5-HB)") (class "Default")
      (node (ref "C5") (pin "1") (pinfunction "1_1") (pintype "passive"))
      (node (ref "IC5") (pin "2") (pinfunction "HB_2") (pintype "passive"))
      (node (ref "U$9") (pin "K") (pinfunction "C_K") (pintype "passive"))
    )
    (net (code "46") (name "Net-(IC5-IN)") (class "Default")
      (node (ref "IC4") (pin "5") (pinfunction "5_5") (pintype "output"))
      (node (ref "IC5") (pin "8") (pinfunction "IN_8") (pintype "input"))
    )
    (net (code "47") (name "Net-(IC5-RDT)") (class "Default")
      (node (ref "IC5") (pin "6") (pinfunction "RDT_6") (pintype "passive"))
      (node (ref "R11") (pin "2") (pinfunction "2_2") (pintype "passive"))
    )
    (net (code "48") (name "Net-(IC6-Pad3)") (class "Default")
      (node (ref "IC6") (pin "3") (pinfunction "3_3") (pintype "output"))
      (node (ref "R14") (pin "1") (pinfunction "1_1") (pintype "passive"))
    )
    (net (code "49") (name "Net-(IC7-HB)") (class "Default")
      (node (ref "C26") (pin "1") (pinfunction "1_1") (pintype "passive"))
      (node (ref "IC7") (pin "2") (pinfunction "HB_2") (pintype "passive"))
      (node (ref "U$17") (pin "K") (pinfunction "C_K") (pintype "passive"))
    )
    (net (code "50") (name "Net-(IC7-IN)") (class "Default")
      (node (ref "IC6") (pin "5") (pinfunction "5_5") (pintype "output"))
      (node (ref "IC7") (pin "8") (pinfunction "IN_8") (pintype "input"))
    )
    (net (code "51") (name "Net-(IC7-RDT)") (class "Default")
      (node (ref "IC7") (pin "6") (pinfunction "RDT_6") (pintype "passive"))
      (node (ref "R17") (pin "2") (pinfunction "2_2") (pintype "passive"))
    )
    (net (code "52") (name "Net-(IC9-Pad3)") (class "Default")
      (node (ref "IC9") (pin "3") (pinfunction "3_3") (pintype "output"))
      (node (ref "R23") (pin "1") (pinfunction "1_1") (pintype "passive"))
    )
    (net (code "53") (name "Net-(IC10-HB)") (class "Default")
      (node (ref "C15") (pin "1") (pinfunction "1_1") (pintype "passive"))
      (node (ref "IC10") (pin "2") (pinfunction "HB_2") (pintype "passive"))
      (node (ref "U$22") (pin "K") (pinfunction "C_K") (pintype "passive"))
    )
    (net (code "54") (name "Net-(IC10-IN)") (class "Default")
      (node (ref "IC10") (pin "8") (pinfunction "IN_8") (pintype "input"))
      (node (ref "IC12") (pin "5") (pinfunction "5_5") (pintype "output"))
    )
    (net (code "55") (name "Net-(IC10-RDT)") (class "Default")
      (node (ref "IC10") (pin "6") (pinfunction "RDT_6") (pintype "passive"))
      (node (ref "R21") (pin "2") (pinfunction "2_2") (pintype "passive"))
    )
    (net (code "56") (name "Net-(IC11-HB)") (class "Default")
      (node (ref "C24") (pin "1") (pinfunction "1_1") (pintype "passive"))
      (node (ref "IC11") (pin "2") (pinfunction "HB_2") (pintype "passive"))
      (node (ref "U$27") (pin "K") (pinfunction "C_K") (pintype "passive"))
    )
    (net (code "57") (name "Net-(IC11-IN)") (class "Default")
      (node (ref "IC11") (pin "8") (pinfunction "IN_8") (pintype "input"))
      (node (ref "IC9") (pin "5") (pinfunction "5_5") (pintype "output"))
    )
    (net (code "58") (name "Net-(IC11-RDT)") (class "Default")
      (node (ref "IC11") (pin "6") (pinfunction "RDT_6") (pintype "passive"))
      (node (ref "R26") (pin "2") (pinfunction "2_2") (pintype "passive"))
    )
    (net (code "59") (name "Net-(IC12-Pad3)") (class "Default")
      (node (ref "IC12") (pin "3") (pinfunction "3_3") (pintype "output"))
      (node (ref "R7") (pin "1") (pinfunction "1_1") (pintype "passive"))
    )
    (net (code "60") (name "Net-(JP6-Pad2)") (class "Default")
      (node (ref "JP6") (pin "2") (pinfunction "2_2") (pintype "passive"))
      (node (ref "R28") (pin "1") (pinfunction "1_1") (pintype "passive"))
    )
    (net (code "61") (name "Net-(LED3-PadA)") (class "Default")
      (node (ref "LED3") (pin "A") (pinfunction "A_A") (pintype "passive"))
      (node (ref "R44") (pin "1") (pinfunction "1_1") (pintype "passive"))
    )
    (net (code "62") (name "Net-(Q1-PadB)") (class "Default")
      (node (ref "Q1") (pin "B") (pinfunction "B_B") (pintype "passive"))
      (node (ref "R4") (pin "2") (pinfunction "2_2") (pintype "passive"))
      (node (ref "R5") (pin "2") (pinfunction "2_2") (pintype "passive"))
    )
    (net (code "63") (name "Net-(Q1-PadC)") (class "Default")
      (node (ref "Q1") (pin "C") (pinfunction "C_C") (pintype "passive"))
      (node (ref "R6") (pin "2") (pinfunction "2_2") (pintype "passive"))
    )
    (net (code "64") (name "Net-(Q2-PadB)") (class "Default")
      (node (ref "Q2") (pin "B") (pinfunction "B_B") (pintype "passive"))
      (node (ref "R12") (pin "2") (pinfunction "2_2") (pintype "passive"))
      (node (ref "R13") (pin "2") (pinfunction "2_2") (pintype "passive"))
    )
    (net (code "65") (name "Net-(Q2-PadC)") (class "Default")
      (node (ref "Q2") (pin "C") (pinfunction "C_C") (pintype "passive"))
      (node (ref "R14") (pin "2") (pinfunction "2_2") (pintype "passive"))
    )
    (net (code "66") (name "Net-(Q3-PadB)") (class "Default")
      (node (ref "Q3") (pin "B") (pinfunction "B_B") (pintype "passive"))
      (node (ref "R22") (pin "2") (pinfunction "2_2") (pintype "passive"))
      (node (ref "R9") (pin "2") (pinfunction "2_2") (pintype "passive"))
    )
    (net (code "67") (name "Net-(Q3-PadC)") (class "Default")
      (node (ref "Q3") (pin "C") (pinfunction "C_C") (pintype "passive"))
      (node (ref "R23") (pin "2") (pinfunction "2_2") (pintype "passive"))
    )
    (net (code "68") (name "Net-(Q5-PadB)") (class "Default")
      (node (ref "Q5") (pin "B") (pinfunction "B_B") (pintype "passive"))
      (node (ref "R32") (pin "2") (pinfunction "2_2") (pintype "passive"))
      (node (ref "R39") (pin "2") (pinfunction "2_2") (pintype "passive"))
    )
    (net (code "69") (name "Net-(Q5-PadC)") (class "Default")
      (node (ref "Q5") (pin "C") (pinfunction "C_C") (pintype "passive"))
      (node (ref "R7") (pin "2") (pinfunction "2_2") (pintype "passive"))
    )
    (net (code "70") (name "Net-(U$7-G1)") (class "Default")
      (node (ref "D12") (pin "A") (pinfunction "A_A") (pintype "passive"))
      (node (ref "R8") (pin "2") (pinfunction "2_2") (pintype "passive"))
      (node (ref "U$7") (pin "1") (pinfunction "G1_1") (pintype "passive"))
    )
    (net (code "71") (name "Net-(U$8-G1)") (class "Default")
      (node (ref "D13") (pin "A") (pinfunction "A_A") (pintype "passive"))
      (node (ref "R10") (pin "2") (pinfunction "2_2") (pintype "passive"))
      (node (ref "U$8") (pin "1") (pinfunction "G1_1") (pintype "passive"))
    )
    (net (code "72") (name "Net-(U$13A-RS)") (class "Default")
      (node (ref "R27") (pin "2") (pinfunction "2_2") (pintype "passive"))
      (node (ref "U$13") (pin "8") (pinfunction "RS_8") (pintype "bidirectional"))
    )
    (net (code "73") (name "Net-(U$15-G1)") (class "Default")
      (node (ref "D16") (pin "A") (pinfunction "A_A") (pintype "passive"))
      (node (ref "R15") (pin "2") (pinfunction "2_2") (pintype "passive"))
      (node (ref "U$15") (pin "1") (pinfunction "G1_1") (pintype "passive"))
    )
    (net (code "74") (name "Net-(U$16-G1)") (class "Default")
      (node (ref "D17") (pin "A") (pinfunction "A_A") (pintype "passive"))
      (node (ref "R16") (pin "2") (pinfunction "2_2") (pintype "passive"))
      (node (ref "U$16") (pin "1") (pinfunction "G1_1") (pintype "passive"))
    )
    (net (code "75") (name "Net-(U$20-G1)") (class "Default")
      (node (ref "D4") (pin "A") (pinfunction "A_A") (pintype "passive"))
      (node (ref "R18") (pin "2") (pinfunction "2_2") (pintype "passive"))
      (node (ref "U$20") (pin "1") (pinfunction "G1_1") (pintype "passive"))
    )
    (net (code "76") (name "Net-(U$21-G1)") (class "Default")
      (node (ref "D5") (pin "A") (pinfunction "A_A") (pintype "passive"))
      (node (ref "R20") (pin "2") (pinfunction "2_2") (pintype "passive"))
      (node (ref "U$21") (pin "1") (pinfunction "G1_1") (pintype "passive"))
    )
    (net (code "77") (name "Net-(U$25-G1)") (class "Default")
      (node (ref "D8") (pin "A") (pinfunction "A_A") (pintype "passive"))
      (node (ref "R24") (pin "2") (pinfunction "2_2") (pintype "passive"))
      (node (ref "U$25") (pin "1") (pinfunction "G1_1") (pintype "passive"))
    )
    (net (code "78") (name "Net-(U$26-G1)") (class "Default")
      (node (ref "D9") (pin "A") (pinfunction "A_A") (pintype "passive"))
      (node (ref "R25") (pin "2") (pinfunction "2_2") (pintype "passive"))
      (node (ref "U$26") (pin "1") (pinfunction "G1_1") (pintype "passive"))
    )
    (net (code "79") (name "SPI2_MISO") (class "Default")
      (node (ref "IC1") (pin "27") (pinfunction "USART3_RTS/TIM1_CH2N/SPI2_MISO/PB14_27") (pintype "bidirectional"))
      (node (ref "U$30") (pin "2") (pinfunction "2_2") (pintype "passive"))
    )
    (net (code "80") (name "SPI2_MOSI") (class "Default")
      (node (ref "IC1") (pin "28") (pinfunction "SPI2_MOSI/TIM1_CH3N/PB15_28") (pintype "bidirectional"))
      (node (ref "U$30") (pin "3") (pinfunction "3_3") (pintype "passive"))
    )
    (net (code "81") (name "SPI2_SCK") (class "Default")
      (node (ref "IC1") (pin "26") (pinfunction "USART3_CTS/TIM1_CH1N/SPI2_SCK/PB13_26") (pintype "bidirectional"))
      (node (ref "U$30") (pin "4") (pinfunction "4_4") (pintype "passive"))
    )
    (net (code "82") (name "SPI2_SS") (class "Default")
      (node (ref "IC1") (pin "25") (pinfunction "I2C2_SMBA/USART3_CK/TIM1_BKIN/SPI2_NSS/PB12_25") (pintype "bidirectional"))
      (node (ref "U$30") (pin "5") (pinfunction "5_5") (pintype "passive"))
    )
    (net (code "83") (name "TIM2_CH1") (class "Default")
      (node (ref "IC1") (pin "10") (pinfunction "PA0/USART2_CTS/ADC12_IN0/TIM2_CH2_ETR/WKUP_10") (pintype "bidirectional"))
      (node (ref "R9") (pin "1") (pinfunction "1_1") (pintype "passive"))
    )
    (net (code "84") (name "TIM2_CH2") (class "Default")
      (node (ref "IC1") (pin "11") (pinfunction "PA1/USART2_RTS/ADC12_IN1/TIM2_CH2_11") (pintype "bidirectional"))
      (node (ref "R32") (pin "1") (pinfunction "1_1") (pintype "passive"))
    )
    (net (code "85") (name "TIM2_CH3") (class "Default")
      (node (ref "IC1") (pin "12") (pinfunction "PA2/USART2_TX/ADC12_IN2/TIM2_CH2_12") (pintype "bidirectional"))
      (node (ref "R12") (pin "1") (pinfunction "1_1") (pintype "passive"))
    )
    (net (code "86") (name "TIM2_CH4") (class "Default")
      (node (ref "IC1") (pin "13") (pinfunction "PA3/USART2_RX/ADC12_IN3/TIM2_CH4_13") (pintype "bidirectional"))
      (node (ref "R4") (pin "1") (pinfunction "1_1") (pintype "passive"))
    )
    (net (code "87") (name "VCC") (class "Default")
      (node (ref "C21") (pin "+") (pinfunction "+_+") (pintype "passive"))
      (node (ref "C33") (pin "+") (pinfunction "+_+") (pintype "passive"))
      (node (ref "C34") (pin "+") (pinfunction "+_+") (pintype "passive"))
      (node (ref "C8") (pin "1") (pinfunction "1_1") (pintype "passive"))
      (node (ref "D1") (pin "K") (pinfunction "C_K") (pintype "passive"))
      (node (ref "D10") (pin "K") (pinfunction "C_K") (pintype "passive"))
      (node (ref "D14") (pin "K") (pinfunction "C_K") (pintype "passive"))
      (node (ref "D6") (pin "K") (pinfunction "C_K") (pintype "passive"))
      (node (ref "H5") (pin "B3,2") (pinfunction "MOUNT_B3,2") (pintype "passive"))
      (node (ref "IC2") (pin "7") (pinfunction "+VIN_7") (pintype "power_in"))
      (node (ref "U$15") (pin "2") (pinfunction "D1_2") (pintype "passive"))
      (node (ref "U$20") (pin "2") (pinfunction "D1_2") (pintype "passive"))
      (node (ref "U$25") (pin "2") (pinfunction "D1_2") (pintype "passive"))
      (node (ref "U$7") (pin "2") (pinfunction "D1_2") (pintype "passive"))
    )
    (net (code "88") (name "unconnected-(ENC2_1-Pad1)") (class "Default")
      (node (ref "ENC2_1") (pin "1") (pinfunction "1_1") (pintype "passive"))
    )
    (net (code "89") (name "unconnected-(ENC2_1-Pad4)") (class "Default")
      (node (ref "ENC2_1") (pin "4") (pinfunction "4_4") (pintype "passive"))
    )
    (net (code "90") (name "unconnected-(ENC2_1-Pad5)") (class "Default")
      (node (ref "ENC2_1") (pin "5") (pinfunction "5_5") (pintype "passive"))
    )
    (net (code "91") (name "unconnected-(ENC2_1-Pad7)") (class "Default")
      (node (ref "ENC2_1") (pin "7") (pinfunction "7_7") (pintype "passive"))
    )
    (net (code "92") (name "unconnected-(ENC2_1-Pad9)") (class "Default")
      (node (ref "ENC2_1") (pin "9") (pinfunction "9_9") (pintype "passive"))
    )
    (net (code "93") (name "unconnected-(ENC2_1-Pad10)") (class "Default")
      (node (ref "ENC2_1") (pin "10") (pinfunction "10_10") (pintype "passive"))
    )
    (net (code "94") (name "unconnected-(ENC3_-Pad1)") (class "Default")
      (node (ref "ENC3_") (pin "1") (pinfunction "1_1") (pintype "passive"))
    )
    (net (code "95") (name "unconnected-(ENC3_-Pad4)") (class "Default")
      (node (ref "ENC3_") (pin "4") (pinfunction "4_4") (pintype "passive"))
    )
    (net (code "96") (name "unconnected-(ENC3_-Pad5)") (class "Default")
      (node (ref "ENC3_") (pin "5") (pinfunction "5_5") (pintype "passive"))
    )
    (net (code "97") (name "unconnected-(ENC3_-Pad7)") (class "Default")
      (node (ref "ENC3_") (pin "7") (pinfunction "7_7") (pintype "passive"))
    )
    (net (code "98") (name "unconnected-(ENC3_-Pad9)") (class "Default")
      (node (ref "ENC3_") (pin "9") (pinfunction "9_9") (pintype "passive"))
    )
    (net (code "99") (name "unconnected-(ENC3_-Pad10)") (class "Default")
      (node (ref "ENC3_") (pin "10") (pinfunction "10_10") (pintype "passive"))
    )
    (net (code "100") (name "unconnected-(IC1B-PA8{slash}USART1_CK{slash}TIM1_CH1{slash}MCO-Pad29)") (class "Default")
      (node (ref "IC1") (pin "29") (pinfunction "PA8/USART1_CK/TIM1_CH1/MCO_29") (pintype "bidirectional"))
    )
    (net (code "101") (name "unconnected-(IC1B-PA15-Pad38)") (class "Default")
      (node (ref "IC1") (pin "38") (pinfunction "PA15_38") (pintype "bidirectional"))
    )
    (net (code "102") (name "unconnected-(IC1C-PA4{slash}USART2_CK{slash}ADC12_IN4{slash}SPI1_NSS-Pad14)") (class "Default")
      (node (ref "IC1") (pin "14") (pinfunction "PA4/USART2_CK/ADC12_IN4/SPI1_NSS_14") (pintype "bidirectional"))
    )
    (net (code "103") (name "unconnected-(IC1C-PA5{slash}ADC12_IN5{slash}SPI1_SCK-Pad15)") (class "Default")
      (node (ref "IC1") (pin "15") (pinfunction "PA5/ADC12_IN5/SPI1_SCK_15") (pintype "bidirectional"))
    )
    (net (code "104") (name "unconnected-(IC1D-I2C2_SCL{slash}USART3_TX{slash}RM-TIM2_CH3{slash}PB10-Pad21)") (class "Default")
      (node (ref "IC1") (pin "21") (pinfunction "I2C2_SCL/USART3_TX/RM-TIM2_CH3/PB10_21") (pintype "bidirectional"))
    )
    (net (code "105") (name "unconnected-(IC1D-TIM4_CH3{slash}RM-I2C1_SCL{slash}RM-CANRX{slash}PB8-Pad45)") (class "Default")
      (node (ref "IC1") (pin "45") (pinfunction "TIM4_CH3/RM-I2C1_SCL/RM-CANRX/PB8_45") (pintype "bidirectional"))
    )
    (net (code "106") (name "unconnected-(IC1D-TIM4_CH4{slash}RM-I2C1_SDA{slash}RM-CANTX{slash}PB9-Pad46)") (class "Default")
      (node (ref "IC1") (pin "46") (pinfunction "TIM4_CH4/RM-I2C1_SDA/RM-CANTX/PB9_46") (pintype "bidirectional"))
    )
    (net (code "107") (name "unconnected-(IC1E-ADC12_IN8{slash}TIM3_CH3{slash}RM-TIM1_CH2N{slash}PB0-Pad18)") (class "Default")
      (node (ref "IC1") (pin "18") (pinfunction "ADC12_IN8/TIM3_CH3/RM-TIM1_CH2N/PB0_18") (pintype "bidirectional"))
    )
    (net (code "108") (name "unconnected-(IC1E-ADC12_IN9{slash}TIM3_CH4{slash}RM-TIM1_CH3N{slash}PB1-Pad19)") (class "Default")
      (node (ref "IC1") (pin "19") (pinfunction "ADC12_IN9/TIM3_CH4/RM-TIM1_CH3N/PB1_19") (pintype "bidirectional"))
    )
    (net (code "109") (name "unconnected-(IC1E-BOOT1{slash}PB2-Pad20)") (class "Default")
      (node (ref "IC1") (pin "20") (pinfunction "BOOT1/PB2_20") (pintype "bidirectional"))
    )
    (net (code "110") (name "unconnected-(IC1E-RM-TIM2_CH2{slash}RM-SPI1_SCK{slash}PB3-Pad39)") (class "Default")
      (node (ref "IC1") (pin "39") (pinfunction "RM-TIM2_CH2/RM-SPI1_SCK/PB3_39") (pintype "bidirectional"))
    )
    (net (code "111") (name "unconnected-(IC1E-RM-TIM3_CH1{slash}RM-SPI1_MISO{slash}JUNTRAST{slash}PB4-Pad40)") (class "Default")
      (node (ref "IC1") (pin "40") (pinfunction "RM-TIM3_CH1/RM-SPI1_MISO/JUNTRAST/PB4_40") (pintype "bidirectional"))
    )
    (net (code "112") (name "unconnected-(IC1F-PC13{slash}TAMPER-RTC-Pad2)") (class "Default")
      (node (ref "IC1") (pin "2") (pinfunction "PC13/TAMPER-RTC_2") (pintype "bidirectional"))
    )
    (net (code "113") (name "unconnected-(IC1F-PC14{slash}OSC32_IN-Pad3)") (class "Default")
      (node (ref "IC1") (pin "3") (pinfunction "PC14/OSC32_IN_3") (pintype "bidirectional"))
    )
    (net (code "114") (name "unconnected-(IC1F-PC15{slash}OSC32_OUT-Pad4)") (class "Default")
      (node (ref "IC1") (pin "4") (pinfunction "PC15/OSC32_OUT_4") (pintype "bidirectional"))
    )
    (net (code "115") (name "unconnected-(IC2-ON{slash}OFF-Pad5)") (class "Default")
      (node (ref "IC2") (pin "5") (pinfunction "ON/OFF_5") (pintype "input"))
    )
    (net (code "116") (name "unconnected-(IC5-NC-Pad5)") (class "Default")
      (node (ref "IC5") (pin "5") (pinfunction "NC_5") (pintype "no_connect"))
    )
    (net (code "117") (name "unconnected-(IC7-NC-Pad5)") (class "Default")
      (node (ref "IC7") (pin "5") (pinfunction "NC_5") (pintype "no_connect"))
    )
    (net (code "118") (name "unconnected-(IC10-NC-Pad5)") (class "Default")
      (node (ref "IC10") (pin "5") (pinfunction "NC_5") (pintype "no_connect"))
    )
    (net (code "119") (name "unconnected-(IC11-NC-Pad5)") (class "Default")
      (node (ref "IC11") (pin "5") (pinfunction "NC_5") (pintype "no_connect"))
    )
    (net (code "120") (name "unconnected-(SWD-Pad4)") (class "Default")
      (node (ref "SWD") (pin "4") (pinfunction "4_4") (pintype "passive"))
    )
    (net (code "121") (name "unconnected-(U$13A-VREF-Pad5)") (class "Default")
      (node (ref "U$13") (pin "5") (pinfunction "VREF_5") (pintype "bidirectional"))
    )
    (net (code "122") (name "＋3.3V") (class "Default")
      (node (ref "C12") (pin "1") (pinfunction "1_1") (pintype "passive"))
      (node (ref "C13") (pin "1") (pinfunction "1_1") (pintype "passive"))
      (node (ref "C16") (pin "1") (pinfunction "1_1") (pintype "passive"))
      (node (ref "C2") (pin "1") (pinfunction "1_1") (pintype "passive"))
      (node (ref "C28") (pin "+") (pinfunction "+_+") (pintype "passive"))
      (node (ref "C7") (pin "1") (pinfunction "1_1") (pintype "passive"))
      (node (ref "IC12") (pin "6") (pinfunction "VCC_6") (pintype "power_in"))
      (node (ref "IC3") (pin "2") (pinfunction "OUT1_2") (pintype "passive"))
      (node (ref "IC3") (pin "4") (pinfunction "OUT_4") (pintype "passive"))
      (node (ref "IC4") (pin "6") (pinfunction "VCC_6") (pintype "power_in"))
      (node (ref "IC6") (pin "6") (pinfunction "VCC_6") (pintype "power_in"))
      (node (ref "IC9") (pin "6") (pinfunction "VCC_6") (pintype "power_in"))
      (node (ref "R44") (pin "2") (pinfunction "2_2") (pintype "passive"))
    )
  )
)
